# DevBoardSt107.net
KiCad netlist of a schematic drawn in Altium Designer
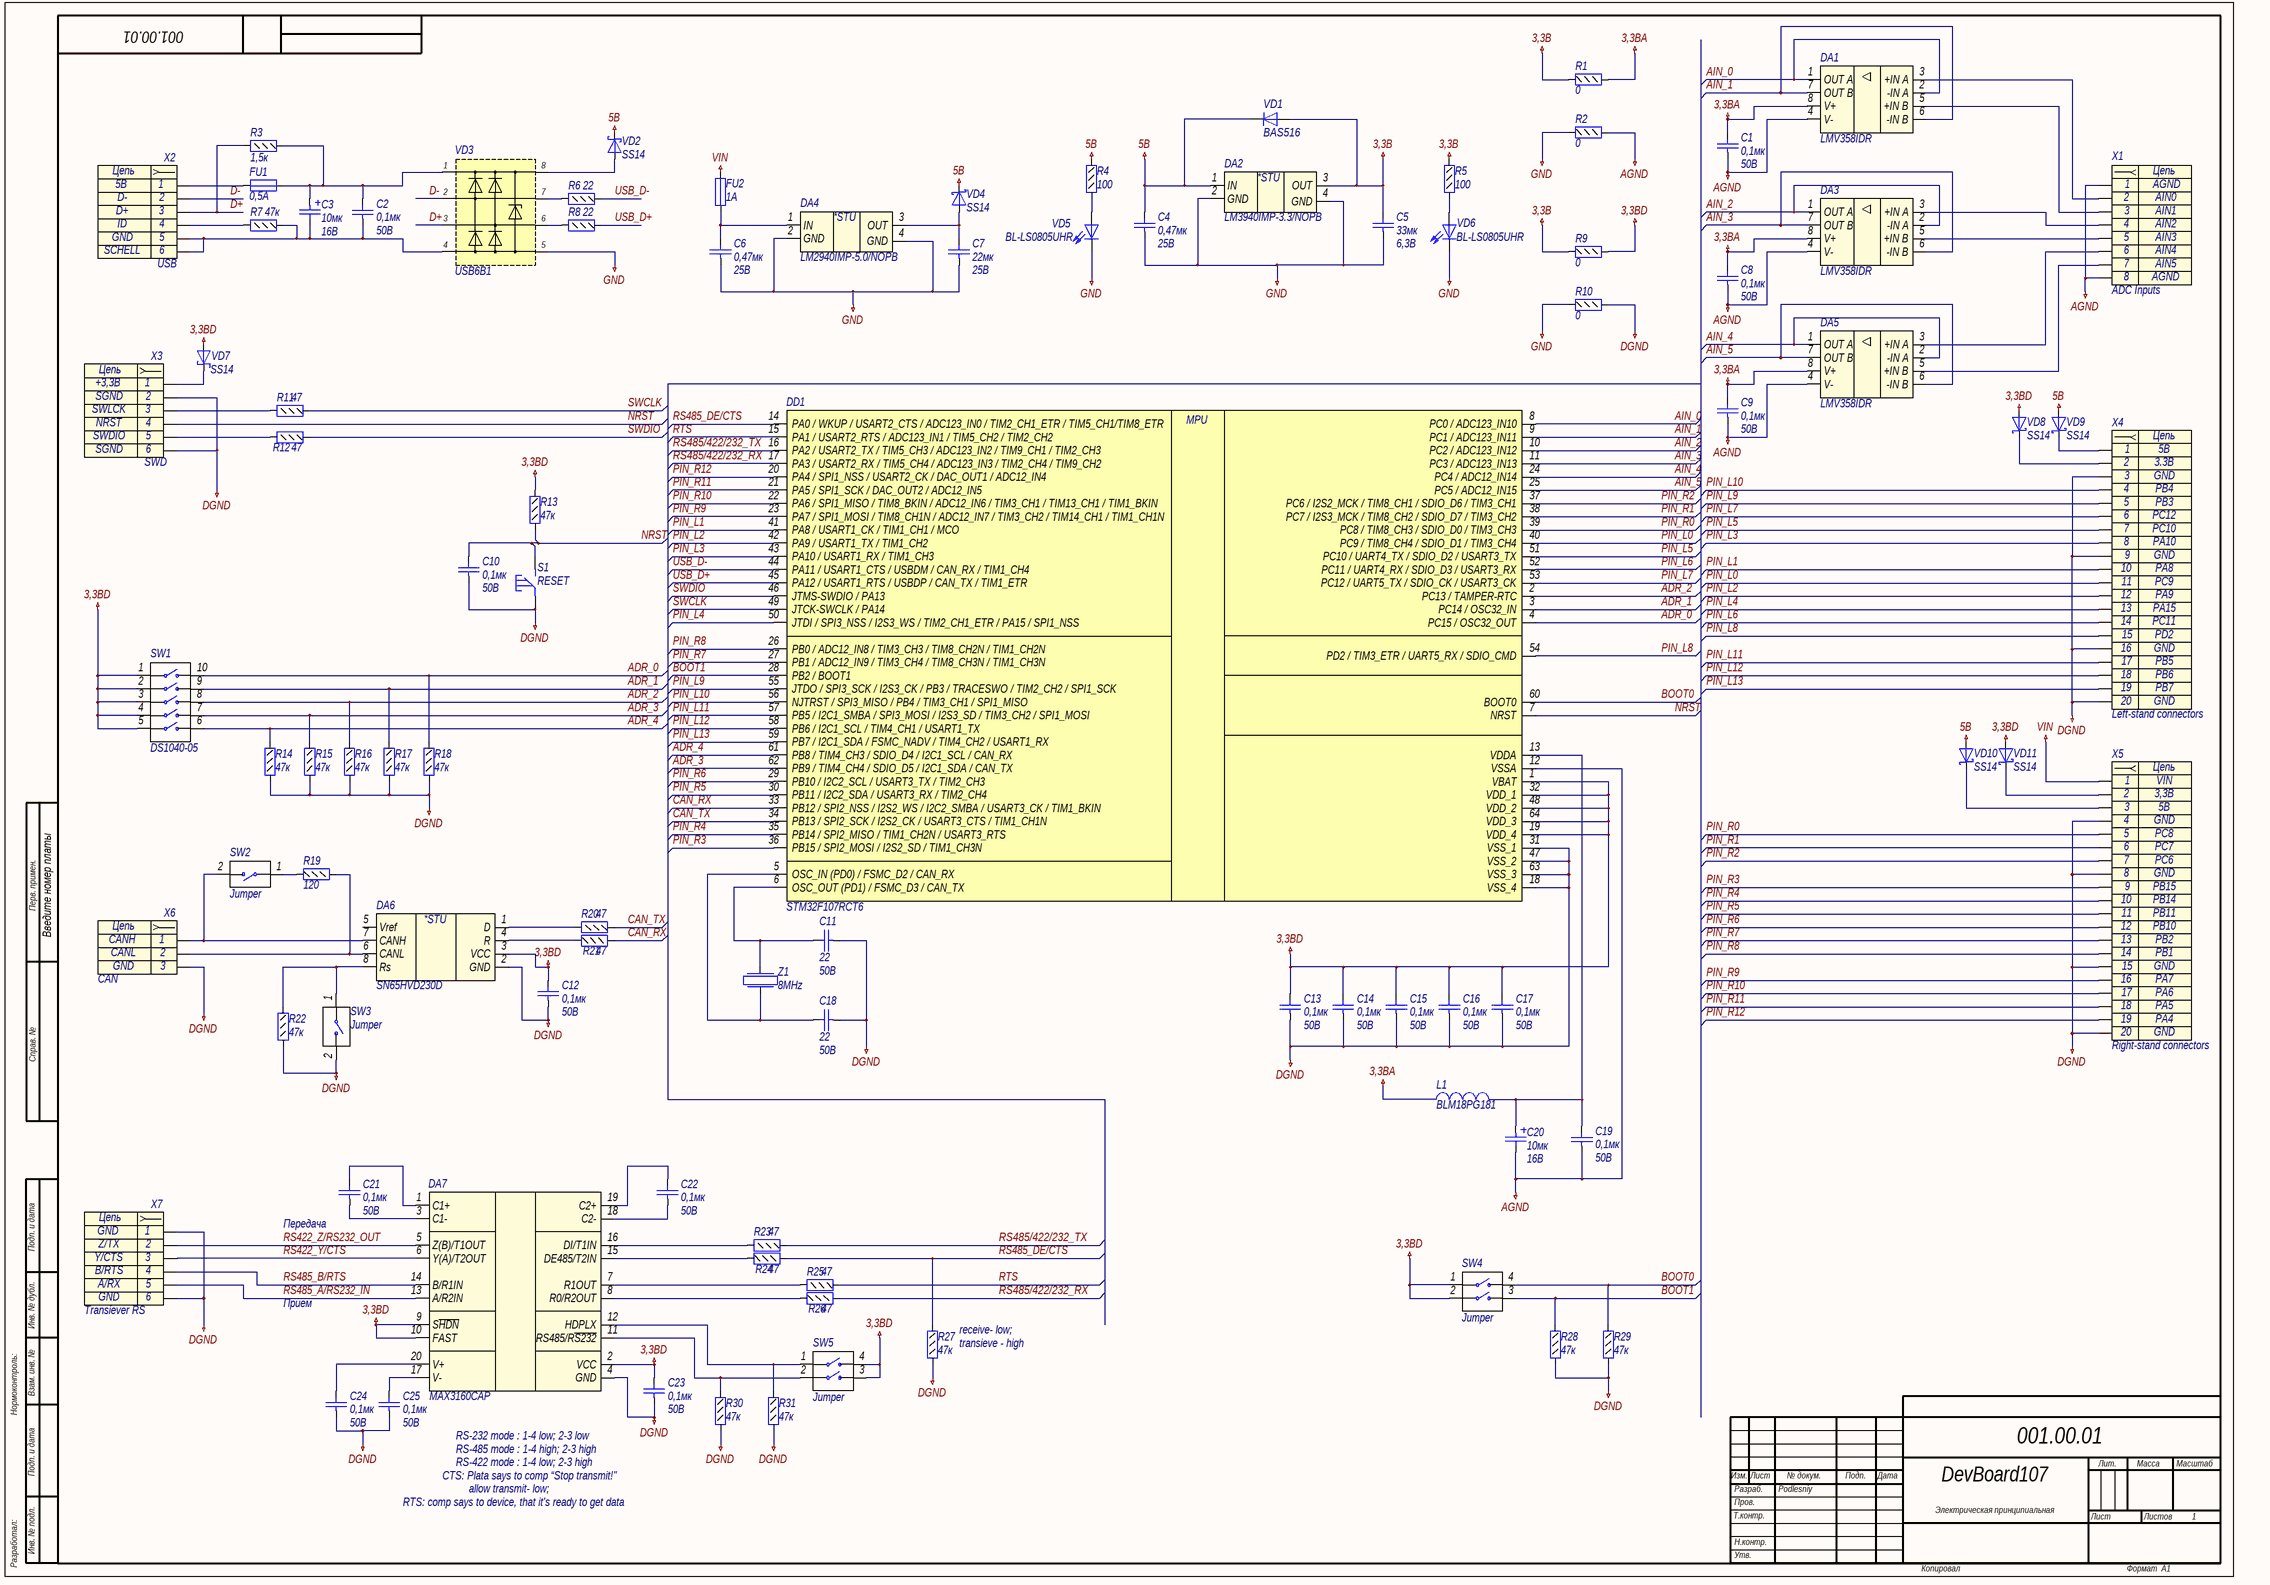
[diagram p0: DevBoardSt107.SchDoc]

(export (version "E")
  (design (tool "Eeschema 10.0.6"))
  (components
    (comp (ref "C1")
      (value "0,1мк")
      (footprint "ZabugorLib:C0603")
      (description "Конденсатор")
      (fields (field (name "VOLTAGE") "50В"))
      (libsource (lib "ZabugorLib") (part "Capacitor"))
    )
    (comp (ref "C2")
      (value "0,1мк")
      (footprint "ZabugorLib:C0603")
      (description "Конденсатор")
      (fields (field (name "VOLTAGE") "50В"))
      (libsource (lib "ZabugorLib") (part "Capacitor"))
    )
    (comp (ref "C3")
      (value "10мк")
      (footprint "ZabugorLib:TANTAL CASE B")
      (description "Конденсатор полярный")
      (fields (field (name "VOLTAGE") "16В"))
      (libsource (lib "ZabugorLib") (part "Capacitor_pol"))
    )
    (comp (ref "C4")
      (value "0,47мк")
      (footprint "ZabugorLib:C0603")
      (description "Конденсатор")
      (fields (field (name "VOLTAGE") "25В"))
      (libsource (lib "ZabugorLib") (part "Capacitor"))
    )
    (comp (ref "C5")
      (value "33мк")
      (footprint "ZabugorLib:C1210")
      (description "Конденсатор")
      (fields (field (name "VOLTAGE") "6,3В"))
      (libsource (lib "ZabugorLib") (part "Capacitor"))
    )
    (comp (ref "C6")
      (value "0,47мк")
      (footprint "ZabugorLib:C0603")
      (description "Конденсатор")
      (fields (field (name "VOLTAGE") "25В"))
      (libsource (lib "ZabugorLib") (part "Capacitor"))
    )
    (comp (ref "C7")
      (value "22мк")
      (footprint "ZabugorLib:C1210")
      (description "Конденсатор")
      (fields (field (name "VOLTAGE") "25В"))
      (libsource (lib "ZabugorLib") (part "Capacitor"))
    )
    (comp (ref "C8")
      (value "0,1мк")
      (footprint "ZabugorLib:C0603")
      (description "Конденсатор")
      (fields (field (name "VOLTAGE") "50В"))
      (libsource (lib "ZabugorLib") (part "Capacitor"))
    )
    (comp (ref "C9")
      (value "0,1мк")
      (footprint "ZabugorLib:C0603")
      (description "Конденсатор")
      (fields (field (name "VOLTAGE") "50В"))
      (libsource (lib "ZabugorLib") (part "Capacitor"))
    )
    (comp (ref "C10")
      (value "0,1мк")
      (footprint "ZabugorLib:C0603")
      (description "Конденсатор")
      (fields (field (name "VOLTAGE") "50В"))
      (libsource (lib "ZabugorLib") (part "Capacitor"))
    )
    (comp (ref "C11")
      (value "22")
      (footprint "ZabugorLib:C0603")
      (description "Конденсатор")
      (fields (field (name "VOLTAGE") "50В"))
      (libsource (lib "ZabugorLib") (part "Capacitor"))
    )
    (comp (ref "C12")
      (value "0,1мк")
      (footprint "ZabugorLib:C0603")
      (description "Конденсатор")
      (fields (field (name "VOLTAGE") "50В"))
      (libsource (lib "ZabugorLib") (part "Capacitor"))
    )
    (comp (ref "C13")
      (value "0,1мк")
      (footprint "ZabugorLib:C0603")
      (description "Конденсатор")
      (fields (field (name "VOLTAGE") "50В"))
      (libsource (lib "ZabugorLib") (part "Capacitor"))
    )
    (comp (ref "C14")
      (value "0,1мк")
      (footprint "ZabugorLib:C0603")
      (description "Конденсатор")
      (fields (field (name "VOLTAGE") "50В"))
      (libsource (lib "ZabugorLib") (part "Capacitor"))
    )
    (comp (ref "C15")
      (value "0,1мк")
      (footprint "ZabugorLib:C0603")
      (description "Конденсатор")
      (fields (field (name "VOLTAGE") "50В"))
      (libsource (lib "ZabugorLib") (part "Capacitor"))
    )
    (comp (ref "C16")
      (value "0,1мк")
      (footprint "ZabugorLib:C0603")
      (description "Конденсатор")
      (fields (field (name "VOLTAGE") "50В"))
      (libsource (lib "ZabugorLib") (part "Capacitor"))
    )
    (comp (ref "C17")
      (value "0,1мк")
      (footprint "ZabugorLib:C0603")
      (description "Конденсатор")
      (fields (field (name "VOLTAGE") "50В"))
      (libsource (lib "ZabugorLib") (part "Capacitor"))
    )
    (comp (ref "C18")
      (value "22")
      (footprint "ZabugorLib:C0603")
      (description "Конденсатор")
      (fields (field (name "VOLTAGE") "50В"))
      (libsource (lib "ZabugorLib") (part "Capacitor"))
    )
    (comp (ref "C19")
      (value "0,1мк")
      (footprint "ZabugorLib:C0603")
      (description "Конденсатор")
      (fields (field (name "VOLTAGE") "50В"))
      (libsource (lib "ZabugorLib") (part "Capacitor"))
    )
    (comp (ref "C20")
      (value "10мк")
      (footprint "ZabugorLib:TANTAL CASE B")
      (description "Конденсатор полярный")
      (fields (field (name "VOLTAGE") "16В"))
      (libsource (lib "ZabugorLib") (part "Capacitor_pol"))
    )
    (comp (ref "C21")
      (value "0,1мк")
      (footprint "ZabugorLib:C0603")
      (description "Конденсатор")
      (fields (field (name "VOLTAGE") "50В"))
      (libsource (lib "ZabugorLib") (part "Capacitor"))
    )
    (comp (ref "C22")
      (value "0,1мк")
      (footprint "ZabugorLib:C0603")
      (description "Конденсатор")
      (fields (field (name "VOLTAGE") "50В"))
      (libsource (lib "ZabugorLib") (part "Capacitor"))
    )
    (comp (ref "C23")
      (value "0,1мк")
      (footprint "ZabugorLib:C0603")
      (description "Конденсатор")
      (fields (field (name "VOLTAGE") "50В"))
      (libsource (lib "ZabugorLib") (part "Capacitor"))
    )
    (comp (ref "C24")
      (value "0,1мк")
      (footprint "ZabugorLib:C0603")
      (description "Конденсатор")
      (fields (field (name "VOLTAGE") "50В"))
      (libsource (lib "ZabugorLib") (part "Capacitor"))
    )
    (comp (ref "C25")
      (value "0,1мк")
      (footprint "ZabugorLib:C0603")
      (description "Конденсатор")
      (fields (field (name "VOLTAGE") "50В"))
      (libsource (lib "ZabugorLib") (part "Capacitor"))
    )
    (comp (ref "DA1")
      (value "LMV358IDR")
      (footprint "ZabugorLib:SO8")
      (description "Операционный усилитель ±6В")
      (libsource (lib "ZabugorLib") (part "LMV358IDR"))
    )
    (comp (ref "DA2")
      (value "LM3940IMP-3.3/NOPB")
      (footprint "ZabugorLib:SOT-223")
      (description "Low-Dropout Regulator for 5-V to 3.3-V Conversion")
      (libsource (lib "ZabugorLib") (part "LM3940"))
    )
    (comp (ref "DA3")
      (value "LMV358IDR")
      (footprint "ZabugorLib:SO8")
      (description "Операционный усилитель ±6В")
      (libsource (lib "ZabugorLib") (part "LMV358IDR"))
    )
    (comp (ref "DA4")
      (value "LM2940IMP-5.0/NOPB")
      (footprint "ZabugorLib:SOT-223")
      (description "Low-Dropout Regulator for 5-V to 3.3-V Conversion")
      (libsource (lib "ZabugorLib") (part "LM2940"))
    )
    (comp (ref "DA5")
      (value "LMV358IDR")
      (footprint "ZabugorLib:SO8")
      (description "Операционный усилитель ±6В")
      (libsource (lib "ZabugorLib") (part "LMV358IDR"))
    )
    (comp (ref "DA6")
      (value "SN65HVD230D")
      (footprint "ZabugorLib:SO8")
      (description "3,3V CAN TRANSCEIVERS")
      (libsource (lib "ZabugorLib") (part "SN65HVD23x"))
    )
    (comp (ref "DA7")
      (value "MAX3160CAP")
      (footprint "ZabugorLib:SSOP20")
      (description "райвер приемопередатчика RS232/RS422/RS485")
      (libsource (lib "ZabugorLib") (part "MAX3160"))
    )
    (comp (ref "DD1")
      (value "STM32F107RCT6")
      (footprint "ZabugorLib:LQFP64")
      (description "Микроконтроллер 64-pin")
      (fields (field (name "NAME") "STM32F107RCT6"))
      (libsource (lib "ZabugorLib") (part "STM32F107RCT6"))
    )
    (comp (ref "FU1")
      (value "0,5A")
      (footprint "FUSE812")
      (description "Предохранитель")
      (fields (field (name "Comment") "MF-MSMF050"))
      (libsource (lib "") (part "Fuse_1"))
    )
    (comp (ref "FU2")
      (value "1A")
      (footprint "FUSE812")
      (description "Предохранитель")
      (fields (field (name "Comment") "MF-MSMF075"))
      (libsource (lib "ZabugorLib") (part "Fuse"))
    )
    (comp (ref "L1")
      (value "XXX")
      (footprint "ZabugorLib:L0603")
      (description "Катушка индуктивности")
      (fields (field (name "NAME") "BLM18PG181"))
      (libsource (lib "ZabugorLib") (part "Inductor"))
    )
    (comp (ref "R1")
      (value "0")
      (footprint "ZabugorLib:R0603")
      (description "Резистор")
      (libsource (lib "") (part "Resistor_0,05Вт_1"))
    )
    (comp (ref "R2")
      (value "0")
      (footprint "ZabugorLib:R0603")
      (description "Резистор")
      (libsource (lib "") (part "Resistor_0,05Вт_1"))
    )
    (comp (ref "R3")
      (value "1,5к")
      (footprint "ZabugorLib:R0603")
      (description "Резистор")
      (libsource (lib "") (part "Resistor_0,05Вт_2"))
    )
    (comp (ref "R4")
      (value "100")
      (footprint "ZabugorLib:R0603")
      (description "Резистор")
      (libsource (lib "ZabugorLib") (part "Resistor_0,05Вт"))
    )
    (comp (ref "R5")
      (value "100")
      (footprint "ZabugorLib:R0603")
      (description "Резистор")
      (libsource (lib "ZabugorLib") (part "Resistor_0,05Вт"))
    )
    (comp (ref "R6")
      (value "22")
      (footprint "ZabugorLib:R0603")
      (description "Резистор")
      (libsource (lib "") (part "Resistor_0,05Вт_2"))
    )
    (comp (ref "R7")
      (value "47к")
      (footprint "ZabugorLib:R0603")
      (description "Резистор")
      (libsource (lib "") (part "Resistor_0,05Вт_2"))
    )
    (comp (ref "R8")
      (value "22")
      (footprint "ZabugorLib:R0603")
      (description "Резистор")
      (libsource (lib "") (part "Resistor_0,05Вт_2"))
    )
    (comp (ref "R9")
      (value "0")
      (footprint "ZabugorLib:R0603")
      (description "Резистор")
      (libsource (lib "") (part "Resistor_0,05Вт_1"))
    )
    (comp (ref "R10")
      (value "0")
      (footprint "ZabugorLib:R0603")
      (description "Резистор")
      (libsource (lib "") (part "Resistor_0,05Вт_1"))
    )
    (comp (ref "R11")
      (value "47")
      (footprint "ZabugorLib:R0603")
      (description "Резистор")
      (libsource (lib "") (part "Resistor_0,05Вт_2"))
    )
    (comp (ref "R12")
      (value "47")
      (footprint "ZabugorLib:R0603")
      (description "Резистор")
      (libsource (lib "") (part "Resistor_0,05Вт_2"))
    )
    (comp (ref "R13")
      (value "47к")
      (footprint "ZabugorLib:R0603")
      (description "Резистор")
      (libsource (lib "ZabugorLib") (part "Resistor_0,05Вт"))
    )
    (comp (ref "R14")
      (value "47к")
      (footprint "ZabugorLib:R0603")
      (description "Резистор")
      (libsource (lib "ZabugorLib") (part "Resistor_0,05Вт"))
    )
    (comp (ref "R15")
      (value "47к")
      (footprint "ZabugorLib:R0603")
      (description "Резистор")
      (libsource (lib "ZabugorLib") (part "Resistor_0,05Вт"))
    )
    (comp (ref "R16")
      (value "47к")
      (footprint "ZabugorLib:R0603")
      (description "Резистор")
      (libsource (lib "ZabugorLib") (part "Resistor_0,05Вт"))
    )
    (comp (ref "R17")
      (value "47к")
      (footprint "ZabugorLib:R0603")
      (description "Резистор")
      (libsource (lib "ZabugorLib") (part "Resistor_0,05Вт"))
    )
    (comp (ref "R18")
      (value "47к")
      (footprint "ZabugorLib:R0603")
      (description "Резистор")
      (libsource (lib "ZabugorLib") (part "Resistor_0,05Вт"))
    )
    (comp (ref "R19")
      (value "120")
      (footprint "ZabugorLib:R0603")
      (description "Резистор")
      (libsource (lib "") (part "Resistor_0,05Вт_1"))
    )
    (comp (ref "R20")
      (value "47")
      (footprint "ZabugorLib:R0603")
      (description "Резистор")
      (libsource (lib "") (part "Resistor_0,05Вт_2"))
    )
    (comp (ref "R21")
      (value "47")
      (footprint "ZabugorLib:R0603")
      (description "Резистор")
      (libsource (lib "") (part "Resistor_0,05Вт_1"))
    )
    (comp (ref "R22")
      (value "47к")
      (footprint "ZabugorLib:R0603")
      (description "Резистор")
      (libsource (lib "ZabugorLib") (part "Resistor_0,05Вт"))
    )
    (comp (ref "R23")
      (value "47")
      (footprint "ZabugorLib:R0603")
      (description "Резистор")
      (libsource (lib "") (part "Resistor_0,05Вт_2"))
    )
    (comp (ref "R24")
      (value "47")
      (footprint "ZabugorLib:R0603")
      (description "Резистор")
      (libsource (lib "") (part "Resistor_0,05Вт_1"))
    )
    (comp (ref "R25")
      (value "47")
      (footprint "ZabugorLib:R0603")
      (description "Резистор")
      (libsource (lib "") (part "Resistor_0,05Вт_2"))
    )
    (comp (ref "R26")
      (value "47")
      (footprint "ZabugorLib:R0603")
      (description "Резистор")
      (libsource (lib "") (part "Resistor_0,05Вт_1"))
    )
    (comp (ref "R27")
      (value "47к")
      (footprint "ZabugorLib:R0603")
      (description "Резистор")
      (libsource (lib "ZabugorLib") (part "Resistor_0,05Вт"))
    )
    (comp (ref "R28")
      (value "47к")
      (footprint "ZabugorLib:R0603")
      (description "Резистор")
      (libsource (lib "ZabugorLib") (part "Resistor_0,05Вт"))
    )
    (comp (ref "R29")
      (value "47к")
      (footprint "ZabugorLib:R0603")
      (description "Резистор")
      (libsource (lib "ZabugorLib") (part "Resistor_0,05Вт"))
    )
    (comp (ref "R30")
      (value "47к")
      (footprint "ZabugorLib:R0603")
      (description "Резистор")
      (libsource (lib "ZabugorLib") (part "Resistor_0,05Вт"))
    )
    (comp (ref "R31")
      (value "47к")
      (footprint "ZabugorLib:R0603")
      (description "Резистор")
      (libsource (lib "ZabugorLib") (part "Resistor_0,05Вт"))
    )
    (comp (ref "S1")
      (value "RESET")
      (footprint "ZabugorLib:DTSM 32")
      (description "Кнопка")
      (fields (field (name "NAME") "RESET"))
      (libsource (lib "ZabugorLib") (part "Button_SMD"))
    )
    (comp (ref "SW1")
      (value "DS1040-05")
      (footprint "ZabugorLib:DIP5")
      (description "DIP переключатель")
      (libsource (lib "ZabugorLib") (part "Switch 5-pin SMD"))
    )
    (comp (ref "SW2")
      (value "Jumper")
      (footprint "ZabugorLib:PLS2-2")
      (description "DIP переключатель")
      (libsource (lib "ZabugorLib") (part "Switch 1-pin SMD"))
    )
    (comp (ref "SW3")
      (value "Jumper")
      (footprint "ZabugorLib:PLS2-2")
      (description "DIP переключатель")
      (libsource (lib "ZabugorLib") (part "Switch 1-pin SMD"))
    )
    (comp (ref "SW4")
      (value "Jumper")
      (footprint "ZabugorLib:PLS2-4")
      (description "Переключатель адреса")
      (libsource (lib "ZabugorLib") (part "Switch 2-pin SMD"))
    )
    (comp (ref "SW5")
      (value "Jumper")
      (footprint "ZabugorLib:PLS2-4")
      (description "Переключатель адреса")
      (libsource (lib "ZabugorLib") (part "Switch 2-pin SMD"))
    )
    (comp (ref "VD1")
      (value "BAS516")
      (footprint "ZabugorLib:SOD523")
      (description "Диод")
      (libsource (lib "ZabugorLib") (part "Diode"))
    )
    (comp (ref "VD2")
      (value "SS14")
      (footprint "Zabugorlib:SMA")
      (description "Диод Шоттки")
      (libsource (lib "ZabugorLib") (part "DiodeSchottky"))
    )
    (comp (ref "VD3")
      (value "USB6B1")
      (footprint "ZabugorLib:SO8")
      (description "Защита линии данных")
      (fields (field (name "NAME") "USB6B1"))
      (libsource (lib "ZabugorLib") (part "USB6B1"))
    )
    (comp (ref "VD4")
      (value "SS14")
      (footprint "Zabugorlib:SMA")
      (description "Диод Шоттки")
      (libsource (lib "ZabugorLib") (part "DiodeSchottky"))
    )
    (comp (ref "VD5")
      (value "BL-LS0805UHR")
      (footprint "ZabugorLib:D0805")
      (description "Светодиод")
      (fields (field (name "NAME") "BL-LS0805UHR"))
      (libsource (lib "ZabugorLib") (part "LED_L"))
    )
    (comp (ref "VD6")
      (value "BL-LS0805UHR")
      (footprint "ZabugorLib:D0805")
      (description "Светодиод")
      (fields (field (name "NAME") "BL-LS0805UHR"))
      (libsource (lib "ZabugorLib") (part "LED_L"))
    )
    (comp (ref "VD7")
      (value "SS14")
      (footprint "Zabugorlib:SMA")
      (description "Диод Шоттки")
      (libsource (lib "ZabugorLib") (part "DiodeSchottky"))
    )
    (comp (ref "VD8")
      (value "SS14")
      (footprint "Zabugorlib:SMA")
      (description "Диод Шоттки")
      (libsource (lib "ZabugorLib") (part "DiodeSchottky"))
    )
    (comp (ref "VD9")
      (value "SS14")
      (footprint "Zabugorlib:SMA")
      (description "Диод Шоттки")
      (libsource (lib "ZabugorLib") (part "DiodeSchottky"))
    )
    (comp (ref "VD10")
      (value "SS14")
      (footprint "Zabugorlib:SMA")
      (description "Диод Шоттки")
      (libsource (lib "ZabugorLib") (part "DiodeSchottky"))
    )
    (comp (ref "VD11")
      (value "SS14")
      (footprint "Zabugorlib:SMA")
      (description "Диод Шоттки")
      (libsource (lib "ZabugorLib") (part "DiodeSchottky"))
    )
    (comp (ref "X1")
      (value "ADC Inputs")
      (footprint "ZabugorLib:PLS-8")
      (description "Разъем - 8 конт. розетка")
      (libsource (lib "ZabugorLib") (part "Header_8_sct"))
    )
    (comp (ref "X2")
      (value "USB")
      (footprint "ZabugorLib:USB-B Micro")
      (description "Разъем - 5 конт. розетка")
      (libsource (lib "ZabugorLib") (part "Header_6_sct"))
    )
    (comp (ref "X3")
      (value "SWD")
      (footprint "ZabugorLib:PLS2-6")
      (description "Разъем - 5 конт. розетка")
      (libsource (lib "ZabugorLib") (part "Header_6_sct"))
    )
    (comp (ref "X4")
      (value "Left-stand connectors")
      (footprint "ZabugorLib:PLS-20-2")
      (description "Разъем - 20 конт. розетка")
      (libsource (lib "ZabugorLib") (part "Header_20"))
    )
    (comp (ref "X5")
      (value "Right-stand connectors")
      (footprint "ZabugorLib:PLS-20-2")
      (description "Разъем - 20 конт. розетка")
      (libsource (lib "ZabugorLib") (part "Header_20"))
    )
    (comp (ref "X6")
      (value "CAN")
      (footprint "ZabugorLib:TERMINAL 3 way-2.54mm")
      (description "Разъем - 2 конт. розетка")
      (libsource (lib "ZabugorLib") (part "Header_3_sct"))
    )
    (comp (ref "X7")
      (value "Transiever RS")
      (footprint "ZabugorLib:TERMINAL 6 way-2.54mm")
      (description "Разъем - 5 конт. розетка")
      (libsource (lib "ZabugorLib") (part "Header_6_sct"))
    )
    (comp (ref "Z1")
      (value "8MHz")
      (footprint "ZabugorLib:QSMD5.0x3.2x1.0")
      (description "Кварцевый резонатор")
      (libsource (lib "ZabugorLib") (part "Crystal"))
    )
  )
  (nets
    (net (code "1") (name "/ADR_0") (class "Default")
      (node (ref "DD1") (pin "4") (pinfunction "PC15_/_OSC32_OUT_4") (pintype "passive"))
      (node (ref "R18") (pin "2") (pinfunction "5_2") (pintype "passive"))
      (node (ref "SW1") (pin "10") (pintype "passive"))
    )
    (net (code "2") (name "/ADR_1") (class "Default")
      (node (ref "DD1") (pin "3") (pinfunction "PC14_/_OSC32_IN_3") (pintype "passive"))
      (node (ref "R17") (pin "2") (pinfunction "5_2") (pintype "passive"))
      (node (ref "SW1") (pin "9") (pintype "passive"))
    )
    (net (code "3") (name "/ADR_2") (class "Default")
      (node (ref "DD1") (pin "2") (pinfunction "PC13_/_TAMPER-RTC_2") (pintype "passive"))
      (node (ref "R16") (pin "2") (pinfunction "5_2") (pintype "passive"))
      (node (ref "SW1") (pin "8") (pintype "passive"))
    )
    (net (code "4") (name "/ADR_3") (class "Default")
      (node (ref "DD1") (pin "62") (pinfunction "PB9_/_TIM4_CH4_/_SDIO_D5_/_I2C1_SDA_/_CAN_TX_62") (pintype "passive"))
      (node (ref "R15") (pin "2") (pinfunction "5_2") (pintype "passive"))
      (node (ref "SW1") (pin "7") (pintype "passive"))
    )
    (net (code "5") (name "/ADR_4") (class "Default")
      (node (ref "DD1") (pin "61") (pinfunction "PB8_/_TIM4_CH3_/_SDIO_D4_/_I2C1_SCL_/_CAN_RX_61") (pintype "passive"))
      (node (ref "R14") (pin "2") (pinfunction "5_2") (pintype "passive"))
      (node (ref "SW1") (pin "6") (pintype "passive"))
    )
    (net (code "6") (name "/AIN_0") (class "Default")
      (node (ref "DA1") (pin "1") (pinfunction "OUT_A_1") (pintype "passive"))
      (node (ref "DA1") (pin "2") (pinfunction "-IN_A_2") (pintype "passive"))
      (node (ref "DD1") (pin "8") (pinfunction "PC0_/_ADC123_IN10_8") (pintype "passive"))
    )
    (net (code "7") (name "/AIN_1") (class "Default")
      (node (ref "DA1") (pin "6") (pinfunction "-IN_B_6") (pintype "passive"))
      (node (ref "DA1") (pin "7") (pinfunction "OUT_B_7") (pintype "passive"))
      (node (ref "DD1") (pin "9") (pinfunction "PC1_/_ADC123_IN11_9") (pintype "passive"))
    )
    (net (code "8") (name "/AIN_2") (class "Default")
      (node (ref "DA3") (pin "1") (pinfunction "OUT_A_1") (pintype "passive"))
      (node (ref "DA3") (pin "2") (pinfunction "-IN_A_2") (pintype "passive"))
      (node (ref "DD1") (pin "10") (pinfunction "PC2_/_ADC123_IN12_10") (pintype "passive"))
    )
    (net (code "9") (name "/AIN_3") (class "Default")
      (node (ref "DA3") (pin "6") (pinfunction "-IN_B_6") (pintype "passive"))
      (node (ref "DA3") (pin "7") (pinfunction "OUT_B_7") (pintype "passive"))
      (node (ref "DD1") (pin "11") (pinfunction "PC3_/_ADC123_IN13_11") (pintype "passive"))
    )
    (net (code "10") (name "/AIN_4") (class "Default")
      (node (ref "DA5") (pin "1") (pinfunction "OUT_A_1") (pintype "passive"))
      (node (ref "DA5") (pin "2") (pinfunction "-IN_A_2") (pintype "passive"))
      (node (ref "DD1") (pin "24") (pinfunction "PC4_/_ADC12_IN14_24") (pintype "passive"))
    )
    (net (code "11") (name "/AIN_5") (class "Default")
      (node (ref "DA5") (pin "6") (pinfunction "-IN_B_6") (pintype "passive"))
      (node (ref "DA5") (pin "7") (pinfunction "OUT_B_7") (pintype "passive"))
      (node (ref "DD1") (pin "25") (pinfunction "PC5_/_ADC12_IN15_25") (pintype "passive"))
    )
    (net (code "12") (name "/BOOT0") (class "Default")
      (node (ref "DD1") (pin "60") (pinfunction "BOOT0_60") (pintype "passive"))
      (node (ref "R29") (pin "2") (pinfunction "5_2") (pintype "passive"))
      (node (ref "SW4") (pin "4") (pintype "passive"))
    )
    (net (code "13") (name "/BOOT1") (class "Default")
      (node (ref "DD1") (pin "28") (pinfunction "PB2_/_BOOT1_28") (pintype "passive"))
      (node (ref "R28") (pin "2") (pinfunction "5_2") (pintype "passive"))
      (node (ref "SW4") (pin "3") (pintype "passive"))
    )
    (net (code "14") (name "/CAN_RX") (class "Default")
      (node (ref "DD1") (pin "33") (pinfunction "PB12_/_SPI2_NSS_/_I2S2_WS_/_I2C2_SMBA_/_USART3_CK_/_TIM1_BKIN_33") (pintype "passive"))
      (node (ref "R21") (pin "1") (pinfunction "1_1") (pintype "passive"))
    )
    (net (code "15") (name "/CAN_TX") (class "Default")
      (node (ref "DD1") (pin "34") (pinfunction "PB13_/_SPI2_SCK_/_I2S2_CK_/_USART3_CTS_/_TIM1_CH1N_34") (pintype "passive"))
      (node (ref "R20") (pin "2") (pinfunction "5_2") (pintype "passive"))
    )
    (net (code "16") (name "/D+") (class "Default")
      (node (ref "R3") (pin "1") (pinfunction "1_1") (pintype "passive"))
      (node (ref "VD3") (pin "3") (pintype "passive"))
      (node (ref "X2") (pin "3") (pinfunction "3_3") (pintype "passive"))
    )
    (net (code "17") (name "/D-") (class "Default")
      (node (ref "VD3") (pin "2") (pintype "passive"))
      (node (ref "X2") (pin "2") (pinfunction "2_2") (pintype "passive"))
    )
    (net (code "18") (name "/NRST") (class "Default")
      (node (ref "C10") (pin "2") (pinfunction "2_2") (pintype "passive"))
      (node (ref "DD1") (pin "7") (pinfunction "NRST_7") (pintype "passive"))
      (node (ref "R13") (pin "1") (pinfunction "1_1") (pintype "passive"))
      (node (ref "S1") (pin "4") (pinfunction "4_4") (pintype "passive"))
      (node (ref "X3") (pin "4") (pinfunction "4_4") (pintype "passive"))
    )
    (net (code "19") (name "/PIN_L0") (class "Default")
      (node (ref "DD1") (pin "40") (pinfunction "PC9_/_TIM8_CH4_/_SDIO_D1_/_TIM3_CH4_40") (pintype "passive"))
      (node (ref "X4") (pin "11") (pinfunction "11_11") (pintype "passive"))
    )
    (net (code "20") (name "/PIN_L1") (class "Default")
      (node (ref "DD1") (pin "41") (pinfunction "PA8_/_USART1_CK_/_TIM1_CH1_/_MCO_41") (pintype "passive"))
      (node (ref "X4") (pin "10") (pinfunction "10_10") (pintype "passive"))
    )
    (net (code "21") (name "/PIN_L2") (class "Default")
      (node (ref "DD1") (pin "42") (pinfunction "PA9_/_USART1_TX_/_TIM1_CH2_42") (pintype "passive"))
      (node (ref "X4") (pin "12") (pinfunction "12_12") (pintype "passive"))
    )
    (net (code "22") (name "/PIN_L3") (class "Default")
      (node (ref "DD1") (pin "43") (pinfunction "PA10_/_USART1_RX_/_TIM1_CH3_43") (pintype "passive"))
      (node (ref "X4") (pin "8") (pinfunction "8_8") (pintype "passive"))
    )
    (net (code "23") (name "/PIN_L4") (class "Default")
      (node (ref "DD1") (pin "50") (pinfunction "JTDI_/_SPI3_NSS_/_I2S3_WS_/_TIM2_CH1_ETR_/_PA15_/_SPI1_NSS_50") (pintype "passive"))
      (node (ref "X4") (pin "13") (pinfunction "13_13") (pintype "passive"))
    )
    (net (code "24") (name "/PIN_L5") (class "Default")
      (node (ref "DD1") (pin "51") (pinfunction "PC10_/_UART4_TX_/_SDIO_D2_/_USART3_TX_51") (pintype "passive"))
      (node (ref "X4") (pin "7") (pinfunction "7_7") (pintype "passive"))
    )
    (net (code "25") (name "/PIN_L6") (class "Default")
      (node (ref "DD1") (pin "52") (pinfunction "PC11_/_UART4_RX_/_SDIO_D3_/_USART3_RX_52") (pintype "passive"))
      (node (ref "X4") (pin "14") (pinfunction "14_14") (pintype "passive"))
    )
    (net (code "26") (name "/PIN_L7") (class "Default")
      (node (ref "DD1") (pin "53") (pinfunction "PC12_/_UART5_TX_/_SDIO_CK_/_USART3_CK_53") (pintype "passive"))
      (node (ref "X4") (pin "6") (pinfunction "6_6") (pintype "passive"))
    )
    (net (code "27") (name "/PIN_L8") (class "Default")
      (node (ref "DD1") (pin "54") (pinfunction "PD2_/_TIM3_ETR_/_UART5_RX_/_SDIO_CMD_54") (pintype "passive"))
      (node (ref "X4") (pin "15") (pinfunction "15_15") (pintype "passive"))
    )
    (net (code "28") (name "/PIN_L9") (class "Default")
      (node (ref "DD1") (pin "55") (pinfunction "JTDO_/_SPI3_SCK_/_I2S3_CK_/_PB3_/_TRACESWO_/_TIM2_CH2_/_SPI1_SCK_55") (pintype "passive"))
      (node (ref "X4") (pin "5") (pinfunction "5_5") (pintype "passive"))
    )
    (net (code "29") (name "/PIN_L10") (class "Default")
      (node (ref "DD1") (pin "56") (pinfunction "NJTRST_/_SPI3_MISO_/_PB4_/_TIM3_CH1_/_SPI1_MISO_56") (pintype "passive"))
      (node (ref "X4") (pin "4") (pinfunction "4_4") (pintype "passive"))
    )
    (net (code "30") (name "/PIN_L11") (class "Default")
      (node (ref "DD1") (pin "57") (pinfunction "PB5_/_I2C1_SMBA_/_SPI3_MOSI_/_I2S3_SD_/_TIM3_CH2_/_SPI1_MOSI_57") (pintype "passive"))
      (node (ref "X4") (pin "17") (pinfunction "17_17") (pintype "passive"))
    )
    (net (code "31") (name "/PIN_L12") (class "Default")
      (node (ref "DD1") (pin "58") (pinfunction "PB6_/_I2C1_SCL_/_TIM4_CH1_/_USART1_TX_58") (pintype "passive"))
      (node (ref "X4") (pin "18") (pinfunction "18_18") (pintype "passive"))
    )
    (net (code "32") (name "/PIN_L13") (class "Default")
      (node (ref "DD1") (pin "59") (pinfunction "PB7_/_I2C1_SDA_/_FSMC_NADV_/_TIM4_CH2_/_USART1_RX_59") (pintype "passive"))
      (node (ref "X4") (pin "19") (pinfunction "19_19") (pintype "passive"))
    )
    (net (code "33") (name "/PIN_R0") (class "Default")
      (node (ref "DD1") (pin "39") (pinfunction "PC8_/_TIM8_CH3_/_SDIO_D0_/_TIM3_CH3_39") (pintype "passive"))
      (node (ref "X5") (pin "5") (pinfunction "5_5") (pintype "passive"))
    )
    (net (code "34") (name "/PIN_R1") (class "Default")
      (node (ref "DD1") (pin "38") (pinfunction "PC7_/_I2S3_MCK_/_TIM8_CH2_/_SDIO_D7_/_TIM3_CH2_38") (pintype "passive"))
      (node (ref "X5") (pin "6") (pinfunction "6_6") (pintype "passive"))
    )
    (net (code "35") (name "/PIN_R2") (class "Default")
      (node (ref "DD1") (pin "37") (pinfunction "PC6_/_I2S2_MCK_/_TIM8_CH1_/_SDIO_D6_/_TIM3_CH1_37") (pintype "passive"))
      (node (ref "X5") (pin "7") (pinfunction "7_7") (pintype "passive"))
    )
    (net (code "36") (name "/PIN_R3") (class "Default")
      (node (ref "DD1") (pin "36") (pinfunction "PB15_/_SPI2_MOSI_/_I2S2_SD_/_TIM1_CH3N_36") (pintype "passive"))
      (node (ref "X5") (pin "9") (pinfunction "9_9") (pintype "passive"))
    )
    (net (code "37") (name "/PIN_R4") (class "Default")
      (node (ref "DD1") (pin "35") (pinfunction "PB14_/_SPI2_MISO_/_TIM1_CH2N_/_USART3_RTS_35") (pintype "passive"))
      (node (ref "X5") (pin "10") (pinfunction "10_10") (pintype "passive"))
    )
    (net (code "38") (name "/PIN_R5") (class "Default")
      (node (ref "DD1") (pin "30") (pinfunction "PB11_/_I2C2_SDA_/_USART3_RX_/_TIM2_CH4_30") (pintype "passive"))
      (node (ref "X5") (pin "11") (pinfunction "11_11") (pintype "passive"))
    )
    (net (code "39") (name "/PIN_R6") (class "Default")
      (node (ref "DD1") (pin "29") (pinfunction "PB10_/_I2C2_SCL_/_USART3_TX_/_TIM2_CH3_29") (pintype "passive"))
      (node (ref "X5") (pin "12") (pinfunction "12_12") (pintype "passive"))
    )
    (net (code "40") (name "/PIN_R7") (class "Default")
      (node (ref "DD1") (pin "27") (pinfunction "PB1_/_ADC12_IN9_/_TIM3_CH4_/_TIM8_CH3N_/_TIM1_CH3N_27") (pintype "passive"))
      (node (ref "X5") (pin "13") (pinfunction "13_13") (pintype "passive"))
    )
    (net (code "41") (name "/PIN_R8") (class "Default")
      (node (ref "DD1") (pin "26") (pinfunction "PB0_/_ADC12_IN8_/_TIM3_CH3_/_TIM8_CH2N_/_TIM1_CH2N_26") (pintype "passive"))
      (node (ref "X5") (pin "14") (pinfunction "14_14") (pintype "passive"))
    )
    (net (code "42") (name "/PIN_R9") (class "Default")
      (node (ref "DD1") (pin "23") (pinfunction "PA7_/_SPI1_MOSI_/_TIM8_CH1N_/_ADC12_IN7_/_TIM3_CH2_/_TIM14_CH1_/_TIM1_CH1N_23") (pintype "passive"))
      (node (ref "X5") (pin "16") (pinfunction "16_16") (pintype "passive"))
    )
    (net (code "43") (name "/PIN_R10") (class "Default")
      (node (ref "DD1") (pin "22") (pinfunction "PA6_/_SPI1_MISO_/_TIM8_BKIN_/_ADC12_IN6_/_TIM3_CH1_/_TIM13_CH1_/_TIM1_BKIN_22") (pintype "passive"))
      (node (ref "X5") (pin "17") (pinfunction "17_17") (pintype "passive"))
    )
    (net (code "44") (name "/PIN_R11") (class "Default")
      (node (ref "DD1") (pin "21") (pinfunction "PA5_/_SPI1_SCK_/_DAC_OUT2_/_ADC12_IN5_21") (pintype "passive"))
      (node (ref "X5") (pin "18") (pinfunction "18_18") (pintype "passive"))
    )
    (net (code "45") (name "/PIN_R12") (class "Default")
      (node (ref "DD1") (pin "20") (pinfunction "PA4_/_SPI1_NSS_/_USART2_CK_/_DAC_OUT1_/_ADC12_IN4_20") (pintype "passive"))
      (node (ref "X5") (pin "19") (pinfunction "19_19") (pintype "passive"))
    )
    (net (code "46") (name "/RS422_Y{slash}CTS") (class "Default")
      (node (ref "DA7") (pin "6") (pinfunction "Y(A)/T2OUT_6") (pintype "power_in"))
      (node (ref "X7") (pin "3") (pinfunction "3_3") (pintype "passive"))
    )
    (net (code "47") (name "/RS422_Z{slash}RS232_OUT") (class "Default")
      (node (ref "DA7") (pin "5") (pinfunction "Z(B)/T1OUT_5") (pintype "power_in"))
      (node (ref "X7") (pin "2") (pinfunction "2_2") (pintype "passive"))
    )
    (net (code "48") (name "/RS485_A{slash}RS232_IN") (class "Default")
      (node (ref "DA7") (pin "13") (pinfunction "A/R2IN_13") (pintype "power_in"))
      (node (ref "X7") (pin "5") (pinfunction "5_5") (pintype "passive"))
    )
    (net (code "49") (name "/RS485_B{slash}RTS") (class "Default")
      (node (ref "DA7") (pin "14") (pinfunction "B/R1IN_14") (pintype "power_in"))
      (node (ref "X7") (pin "4") (pinfunction "4_4") (pintype "passive"))
    )
    (net (code "50") (name "/RS485_DE{slash}CTS") (class "Default")
      (node (ref "DD1") (pin "14") (pinfunction "PA0_/_WKUP_/_USART2_CTS_/_ADC123_IN0_/_TIM2_CH1_ETR_/_TIM5_CH1/TIM8_ETR_14") (pintype "passive"))
      (node (ref "R24") (pin "1") (pinfunction "1_1") (pintype "passive"))
      (node (ref "R27") (pin "2") (pinfunction "5_2") (pintype "passive"))
    )
    (net (code "51") (name "/RS485{slash}422{slash}232_RX") (class "Default")
      (node (ref "DD1") (pin "17") (pinfunction "PA3_/_USART2_RX_/_TIM5_CH4_/_ADC123_IN3_/_TIM2_CH4_/_TIM9_CH2_17") (pintype "passive"))
      (node (ref "R26") (pin "1") (pinfunction "1_1") (pintype "passive"))
    )
    (net (code "52") (name "/RS485{slash}422{slash}232_TX") (class "Default")
      (node (ref "DD1") (pin "16") (pinfunction "PA2_/_USART2_TX_/_TIM5_CH3_/_ADC123_IN2_/_TIM9_CH1_/_TIM2_CH3_16") (pintype "passive"))
      (node (ref "R23") (pin "2") (pinfunction "5_2") (pintype "passive"))
    )
    (net (code "53") (name "/RTS") (class "Default")
      (node (ref "DD1") (pin "15") (pinfunction "PA1_/_USART2_RTS_/_ADC123_IN1_/_TIM5_CH2_/_TIM2_CH2_15") (pintype "passive"))
      (node (ref "R25") (pin "2") (pinfunction "5_2") (pintype "passive"))
    )
    (net (code "54") (name "/SWCLK") (class "Default")
      (node (ref "DD1") (pin "49") (pinfunction "JTCK-SWCLK_/_PA14_49") (pintype "passive"))
      (node (ref "R11") (pin "2") (pinfunction "5_2") (pintype "passive"))
    )
    (net (code "55") (name "/SWDIO") (class "Default")
      (node (ref "DD1") (pin "46") (pinfunction "JTMS-SWDIO_/_PA13_46") (pintype "passive"))
      (node (ref "R12") (pin "2") (pinfunction "5_2") (pintype "passive"))
    )
    (net (code "56") (name "/USB_D+") (class "Default")
      (node (ref "DD1") (pin "45") (pinfunction "PA12_/_USART1_RTS_/_USBDP_/_CAN_TX_/_TIM1_ETR_45") (pintype "passive"))
      (node (ref "R8") (pin "2") (pinfunction "5_2") (pintype "passive"))
    )
    (net (code "57") (name "/USB_D-") (class "Default")
      (node (ref "DD1") (pin "44") (pinfunction "PA11_/_USART1_CTS_/_USBDM_/_CAN_RX_/_TIM1_CH4_44") (pintype "passive"))
      (node (ref "R6") (pin "2") (pinfunction "5_2") (pintype "passive"))
    )
    (net (code "58") (name "3,3В") (class "Default")
      (node (ref "C5") (pin "2") (pinfunction "2_2") (pintype "passive"))
      (node (ref "DA2") (pin "3") (pinfunction "OUT_3") (pintype "power_in"))
      (node (ref "R1") (pin "2") (pinfunction "5_2") (pintype "passive"))
      (node (ref "R5") (pin "2") (pinfunction "5_2") (pintype "passive"))
      (node (ref "R9") (pin "2") (pinfunction "5_2") (pintype "passive"))
      (node (ref "VD1") (pin "2") (pinfunction "A_2") (pintype "passive"))
    )
    (net (code "59") (name "3,3ВA") (class "Default")
      (node (ref "C1") (pin "2") (pinfunction "2_2") (pintype "passive"))
      (node (ref "C8") (pin "2") (pinfunction "2_2") (pintype "passive"))
      (node (ref "C9") (pin "2") (pinfunction "2_2") (pintype "passive"))
      (node (ref "DA1") (pin "8") (pinfunction "V+_8") (pintype "passive"))
      (node (ref "DA3") (pin "8") (pinfunction "V+_8") (pintype "passive"))
      (node (ref "DA5") (pin "8") (pinfunction "V+_8") (pintype "passive"))
      (node (ref "L1") (pin "1") (pinfunction "1_1") (pintype "passive"))
      (node (ref "R1") (pin "1") (pinfunction "1_1") (pintype "passive"))
    )
    (net (code "60") (name "3,3ВD") (class "Default")
      (node (ref "C12") (pin "2") (pinfunction "2_2") (pintype "passive"))
      (node (ref "C13") (pin "2") (pinfunction "2_2") (pintype "passive"))
      (node (ref "C14") (pin "2") (pinfunction "2_2") (pintype "passive"))
      (node (ref "C15") (pin "2") (pinfunction "2_2") (pintype "passive"))
      (node (ref "C16") (pin "2") (pinfunction "2_2") (pintype "passive"))
      (node (ref "C17") (pin "2") (pinfunction "2_2") (pintype "passive"))
      (node (ref "C23") (pin "2") (pinfunction "2_2") (pintype "passive"))
      (node (ref "DA6") (pin "3") (pinfunction "VCC_3") (pintype "power_in"))
      (node (ref "DA7") (pin "10") (pinfunction "FAST_10") (pintype "power_in"))
      (node (ref "DA7") (pin "2") (pinfunction "VCC_2") (pintype "power_in"))
      (node (ref "DA7") (pin "9") (pinfunction "S~{HDN}_9") (pintype "power_in"))
      (node (ref "DD1") (pin "1") (pinfunction "VBAT_1") (pintype "passive"))
      (node (ref "DD1") (pin "19") (pinfunction "VDD_4_19") (pintype "passive"))
      (node (ref "DD1") (pin "32") (pinfunction "VDD_1_32") (pintype "passive"))
      (node (ref "DD1") (pin "48") (pinfunction "VDD_2_48") (pintype "passive"))
      (node (ref "DD1") (pin "64") (pinfunction "VDD_3_64") (pintype "passive"))
      (node (ref "R13") (pin "2") (pinfunction "5_2") (pintype "passive"))
      (node (ref "R9") (pin "1") (pinfunction "1_1") (pintype "passive"))
      (node (ref "SW1") (pin "1") (pintype "passive"))
      (node (ref "SW1") (pin "2") (pintype "passive"))
      (node (ref "SW1") (pin "3") (pintype "passive"))
      (node (ref "SW1") (pin "4") (pintype "passive"))
      (node (ref "SW1") (pin "5") (pintype "passive"))
      (node (ref "SW4") (pin "1") (pintype "passive"))
      (node (ref "SW4") (pin "2") (pintype "passive"))
      (node (ref "SW5") (pin "3") (pintype "passive"))
      (node (ref "SW5") (pin "4") (pintype "passive"))
      (node (ref "VD11") (pin "2") (pinfunction "A_2") (pintype "passive"))
      (node (ref "VD7") (pin "2") (pinfunction "A_2") (pintype "passive"))
      (node (ref "VD8") (pin "2") (pinfunction "A_2") (pintype "passive"))
    )
    (net (code "61") (name "5В") (class "Default")
      (node (ref "C4") (pin "2") (pinfunction "2_2") (pintype "passive"))
      (node (ref "DA2") (pin "1") (pinfunction "IN_1") (pintype "power_in"))
      (node (ref "R4") (pin "2") (pinfunction "5_2") (pintype "passive"))
      (node (ref "VD1") (pin "1") (pinfunction "K_1") (pintype "passive"))
      (node (ref "VD10") (pin "2") (pinfunction "A_2") (pintype "passive"))
      (node (ref "VD2") (pin "1") (pinfunction "K_1") (pintype "passive"))
      (node (ref "VD4") (pin "1") (pinfunction "K_1") (pintype "passive"))
      (node (ref "VD9") (pin "2") (pinfunction "A_2") (pintype "passive"))
    )
    (net (code "62") (name "AGND") (class "Default")
      (node (ref "C1") (pin "1") (pinfunction "1_1") (pintype "passive"))
      (node (ref "C19") (pin "1") (pinfunction "1_1") (pintype "passive"))
      (node (ref "C20") (pin "2") (pinfunction "2_2") (pintype "passive"))
      (node (ref "C8") (pin "1") (pinfunction "1_1") (pintype "passive"))
      (node (ref "C9") (pin "1") (pinfunction "1_1") (pintype "passive"))
      (node (ref "DA1") (pin "4") (pinfunction "V-_4") (pintype "passive"))
      (node (ref "DA3") (pin "4") (pinfunction "V-_4") (pintype "passive"))
      (node (ref "DA5") (pin "4") (pinfunction "V-_4") (pintype "passive"))
      (node (ref "DD1") (pin "12") (pinfunction "VSSA_12") (pintype "passive"))
      (node (ref "R2") (pin "1") (pinfunction "1_1") (pintype "passive"))
      (node (ref "X1") (pin "1") (pinfunction "1_1") (pintype "passive"))
      (node (ref "X1") (pin "8") (pinfunction "8_8") (pintype "passive"))
    )
    (net (code "63") (name "DGND") (class "Default")
      (node (ref "C10") (pin "1") (pinfunction "1_1") (pintype "passive"))
      (node (ref "C11") (pin "1") (pinfunction "1_1") (pintype "passive"))
      (node (ref "C12") (pin "1") (pinfunction "1_1") (pintype "passive"))
      (node (ref "C13") (pin "1") (pinfunction "1_1") (pintype "passive"))
      (node (ref "C14") (pin "1") (pinfunction "1_1") (pintype "passive"))
      (node (ref "C15") (pin "1") (pinfunction "1_1") (pintype "passive"))
      (node (ref "C16") (pin "1") (pinfunction "1_1") (pintype "passive"))
      (node (ref "C17") (pin "1") (pinfunction "1_1") (pintype "passive"))
      (node (ref "C18") (pin "1") (pinfunction "1_1") (pintype "passive"))
      (node (ref "C23") (pin "1") (pinfunction "1_1") (pintype "passive"))
      (node (ref "C24") (pin "1") (pinfunction "1_1") (pintype "passive"))
      (node (ref "C25") (pin "1") (pinfunction "1_1") (pintype "passive"))
      (node (ref "DA6") (pin "2") (pinfunction "GND_2") (pintype "power_in"))
      (node (ref "DA7") (pin "4") (pinfunction "GND_4") (pintype "power_in"))
      (node (ref "DD1") (pin "18") (pinfunction "VSS_4_18") (pintype "passive"))
      (node (ref "DD1") (pin "31") (pinfunction "VSS_1_31") (pintype "passive"))
      (node (ref "DD1") (pin "47") (pinfunction "VSS_2_47") (pintype "passive"))
      (node (ref "DD1") (pin "63") (pinfunction "VSS_3_63") (pintype "passive"))
      (node (ref "R10") (pin "1") (pinfunction "1_1") (pintype "passive"))
      (node (ref "R14") (pin "1") (pinfunction "1_1") (pintype "passive"))
      (node (ref "R15") (pin "1") (pinfunction "1_1") (pintype "passive"))
      (node (ref "R16") (pin "1") (pinfunction "1_1") (pintype "passive"))
      (node (ref "R17") (pin "1") (pinfunction "1_1") (pintype "passive"))
      (node (ref "R18") (pin "1") (pinfunction "1_1") (pintype "passive"))
      (node (ref "R22") (pin "1") (pinfunction "1_1") (pintype "passive"))
      (node (ref "R27") (pin "1") (pinfunction "1_1") (pintype "passive"))
      (node (ref "R28") (pin "1") (pinfunction "1_1") (pintype "passive"))
      (node (ref "R29") (pin "1") (pinfunction "1_1") (pintype "passive"))
      (node (ref "R30") (pin "1") (pinfunction "1_1") (pintype "passive"))
      (node (ref "R31") (pin "1") (pinfunction "1_1") (pintype "passive"))
      (node (ref "S1") (pin "1") (pinfunction "1_1") (pintype "passive"))
      (node (ref "SW3") (pin "2") (pintype "passive"))
      (node (ref "X3") (pin "2") (pinfunction "2_2") (pintype "passive"))
      (node (ref "X3") (pin "6") (pinfunction "6_6") (pintype "passive"))
      (node (ref "X4") (pin "16") (pinfunction "16_16") (pintype "passive"))
      (node (ref "X4") (pin "20") (pinfunction "20_20") (pintype "passive"))
      (node (ref "X4") (pin "3") (pinfunction "3_3") (pintype "passive"))
      (node (ref "X4") (pin "9") (pinfunction "9_9") (pintype "passive"))
      (node (ref "X5") (pin "15") (pinfunction "15_15") (pintype "passive"))
      (node (ref "X5") (pin "20") (pinfunction "20_20") (pintype "passive"))
      (node (ref "X5") (pin "4") (pinfunction "4_4") (pintype "passive"))
      (node (ref "X5") (pin "8") (pinfunction "8_8") (pintype "passive"))
      (node (ref "X6") (pin "3") (pinfunction "3_3") (pintype "passive"))
      (node (ref "X7") (pin "1") (pinfunction "1_1") (pintype "passive"))
      (node (ref "X7") (pin "6") (pinfunction "6_6") (pintype "passive"))
    )
    (net (code "64") (name "GND") (class "Default")
      (node (ref "C4") (pin "1") (pinfunction "1_1") (pintype "passive"))
      (node (ref "C5") (pin "1") (pinfunction "1_1") (pintype "passive"))
      (node (ref "C6") (pin "1") (pinfunction "1_1") (pintype "passive"))
      (node (ref "C7") (pin "1") (pinfunction "1_1") (pintype "passive"))
      (node (ref "DA2") (pin "2") (pinfunction "GND_2") (pintype "power_in"))
      (node (ref "DA2") (pin "4") (pinfunction "GND_4") (pintype "power_in"))
      (node (ref "DA4") (pin "2") (pinfunction "GND_2") (pintype "power_in"))
      (node (ref "DA4") (pin "4") (pinfunction "GND_4") (pintype "power_in"))
      (node (ref "R10") (pin "2") (pinfunction "5_2") (pintype "passive"))
      (node (ref "R2") (pin "2") (pinfunction "5_2") (pintype "passive"))
      (node (ref "VD3") (pin "5") (pintype "passive"))
      (node (ref "VD5") (pin "1") (pinfunction "K_1") (pintype "passive"))
      (node (ref "VD6") (pin "1") (pinfunction "K_1") (pintype "passive"))
    )
    (net (code "65") (name "Net-(DA1-+IN_A)") (class "Default")
      (node (ref "DA1") (pin "3") (pinfunction "+IN_A_3") (pintype "passive"))
      (node (ref "X1") (pin "2") (pinfunction "2_2") (pintype "passive"))
    )
    (net (code "66") (name "Net-(DA1-+IN_B)") (class "Default")
      (node (ref "DA1") (pin "5") (pinfunction "+IN_B_5") (pintype "passive"))
      (node (ref "X1") (pin "3") (pinfunction "3_3") (pintype "passive"))
    )
    (net (code "67") (name "Net-(DA3-+IN_A)") (class "Default")
      (node (ref "DA3") (pin "3") (pinfunction "+IN_A_3") (pintype "passive"))
      (node (ref "X1") (pin "4") (pinfunction "4_4") (pintype "passive"))
    )
    (net (code "68") (name "Net-(DA3-+IN_B)") (class "Default")
      (node (ref "DA3") (pin "5") (pinfunction "+IN_B_5") (pintype "passive"))
      (node (ref "X1") (pin "5") (pinfunction "5_5") (pintype "passive"))
    )
    (net (code "69") (name "Net-(DA4-IN)") (class "Default")
      (node (ref "C6") (pin "2") (pinfunction "2_2") (pintype "passive"))
      (node (ref "DA4") (pin "1") (pinfunction "IN_1") (pintype "power_in"))
      (node (ref "FU2") (pin "1") (pinfunction "1_1") (pintype "passive"))
    )
    (net (code "70") (name "Net-(DA4-OUT)") (class "Default")
      (node (ref "C7") (pin "2") (pinfunction "2_2") (pintype "passive"))
      (node (ref "DA4") (pin "3") (pinfunction "OUT_3") (pintype "power_in"))
      (node (ref "VD4") (pin "2") (pinfunction "A_2") (pintype "passive"))
    )
    (net (code "71") (name "Net-(DA5-+IN_A)") (class "Default")
      (node (ref "DA5") (pin "3") (pinfunction "+IN_A_3") (pintype "passive"))
      (node (ref "X1") (pin "6") (pinfunction "6_6") (pintype "passive"))
    )
    (net (code "72") (name "Net-(DA5-+IN_B)") (class "Default")
      (node (ref "DA5") (pin "5") (pinfunction "+IN_B_5") (pintype "passive"))
      (node (ref "X1") (pin "7") (pinfunction "7_7") (pintype "passive"))
    )
    (net (code "73") (name "Net-(DA6-CANH)") (class "Default")
      (node (ref "DA6") (pin "7") (pinfunction "CANH_7") (pintype "power_in"))
      (node (ref "SW2") (pin "2") (pintype "passive"))
      (node (ref "X6") (pin "1") (pinfunction "1_1") (pintype "passive"))
    )
    (net (code "74") (name "Net-(DA6-CANL)") (class "Default")
      (node (ref "DA6") (pin "6") (pinfunction "CANL_6") (pintype "power_in"))
      (node (ref "R19") (pin "1") (pinfunction "1_1") (pintype "passive"))
      (node (ref "X6") (pin "2") (pinfunction "2_2") (pintype "passive"))
    )
    (net (code "75") (name "Net-(DA6-D)") (class "Default")
      (node (ref "DA6") (pin "1") (pinfunction "D_1") (pintype "power_in"))
      (node (ref "R20") (pin "1") (pinfunction "1_1") (pintype "passive"))
    )
    (net (code "76") (name "Net-(DA6-R)") (class "Default")
      (node (ref "DA6") (pin "4") (pinfunction "R_4") (pintype "power_in"))
      (node (ref "R21") (pin "2") (pinfunction "5_2") (pintype "passive"))
    )
    (net (code "77") (name "Net-(DA6-Rs)") (class "Default")
      (node (ref "DA6") (pin "8") (pinfunction "Rs_8") (pintype "power_in"))
      (node (ref "R22") (pin "2") (pinfunction "5_2") (pintype "passive"))
      (node (ref "SW3") (pin "1") (pintype "passive"))
    )
    (net (code "78") (name "Net-(DA7-C1+)") (class "Default")
      (node (ref "C21") (pin "2") (pinfunction "2_2") (pintype "passive"))
      (node (ref "DA7") (pin "1") (pinfunction "C1+_1") (pintype "power_in"))
    )
    (net (code "79") (name "Net-(DA7-C1-)") (class "Default")
      (node (ref "C21") (pin "1") (pinfunction "1_1") (pintype "passive"))
      (node (ref "DA7") (pin "3") (pinfunction "C1-_3") (pintype "power_in"))
    )
    (net (code "80") (name "Net-(DA7-C2+)") (class "Default")
      (node (ref "C22") (pin "2") (pinfunction "2_2") (pintype "passive"))
      (node (ref "DA7") (pin "19") (pinfunction "C2+_19") (pintype "power_in"))
    )
    (net (code "81") (name "Net-(DA7-C2-)") (class "Default")
      (node (ref "C22") (pin "1") (pinfunction "1_1") (pintype "passive"))
      (node (ref "DA7") (pin "18") (pinfunction "C2-_18") (pintype "power_in"))
    )
    (net (code "82") (name "Net-(DA7-DE485{slash}T2IN)") (class "Default")
      (node (ref "DA7") (pin "15") (pinfunction "DE485/T2IN_15") (pintype "power_in"))
      (node (ref "R24") (pin "2") (pinfunction "5_2") (pintype "passive"))
    )
    (net (code "83") (name "Net-(DA7-DI{slash}T1IN)") (class "Default")
      (node (ref "DA7") (pin "16") (pinfunction "DI/T1IN_16") (pintype "power_in"))
      (node (ref "R23") (pin "1") (pinfunction "1_1") (pintype "passive"))
    )
    (net (code "84") (name "Net-(DA7-HDPLX)") (class "Default")
      (node (ref "DA7") (pin "12") (pinfunction "HDPLX_12") (pintype "power_in"))
      (node (ref "R31") (pin "2") (pinfunction "5_2") (pintype "passive"))
      (node (ref "SW5") (pin "1") (pintype "passive"))
    )
    (net (code "85") (name "Net-(DA7-R0{slash}R2OUT)") (class "Default")
      (node (ref "DA7") (pin "8") (pinfunction "R0/R2OUT_8") (pintype "power_in"))
      (node (ref "R26") (pin "2") (pinfunction "5_2") (pintype "passive"))
    )
    (net (code "86") (name "Net-(DA7-R1OUT)") (class "Default")
      (node (ref "DA7") (pin "7") (pinfunction "R1OUT_7") (pintype "power_in"))
      (node (ref "R25") (pin "1") (pinfunction "1_1") (pintype "passive"))
    )
    (net (code "87") (name "Net-(DA7-RS485{slash}R~{S232})") (class "Default")
      (node (ref "DA7") (pin "11") (pinfunction "RS485/R~{S232}_11") (pintype "power_in"))
      (node (ref "R30") (pin "2") (pinfunction "5_2") (pintype "passive"))
      (node (ref "SW5") (pin "2") (pintype "passive"))
    )
    (net (code "88") (name "Net-(DA7-V+)") (class "Default")
      (node (ref "C24") (pin "2") (pinfunction "2_2") (pintype "passive"))
      (node (ref "DA7") (pin "20") (pinfunction "V+_20") (pintype "power_in"))
    )
    (net (code "89") (name "Net-(DA7-V-)") (class "Default")
      (node (ref "C25") (pin "2") (pinfunction "2_2") (pintype "passive"))
      (node (ref "DA7") (pin "17") (pinfunction "V-_17") (pintype "power_in"))
    )
    (net (code "90") (name "Net-(DD1-OSC_IN_(PD0)_{slash}_FSMC_D2_{slash}_CAN_RX)") (class "Default")
      (node (ref "C18") (pin "2") (pinfunction "2_2") (pintype "passive"))
      (node (ref "DD1") (pin "5") (pinfunction "OSC_IN_(PD0)_/_FSMC_D2_/_CAN_RX_5") (pintype "passive"))
      (node (ref "Z1") (pin "1") (pinfunction "1_1") (pintype "passive"))
    )
    (net (code "91") (name "Net-(DD1-OSC_OUT_(PD1)_{slash}_FSMC_D3_{slash}_CAN_TX)") (class "Default")
      (node (ref "C11") (pin "2") (pinfunction "2_2") (pintype "passive"))
      (node (ref "DD1") (pin "6") (pinfunction "OSC_OUT_(PD1)_/_FSMC_D3_/_CAN_TX_6") (pintype "passive"))
      (node (ref "Z1") (pin "2") (pinfunction "2_2") (pintype "passive"))
    )
    (net (code "92") (name "Net-(DD1-VDDA)") (class "Default")
      (node (ref "C19") (pin "2") (pinfunction "2_2") (pintype "passive"))
      (node (ref "C20") (pin "1") (pinfunction "1_1") (pintype "passive"))
      (node (ref "DD1") (pin "13") (pinfunction "VDDA_13") (pintype "passive"))
      (node (ref "L1") (pin "2") (pinfunction "2_2") (pintype "passive"))
    )
    (net (code "93") (name "Net-(FU1-Pad1)") (class "Default")
      (node (ref "FU1") (pin "1") (pinfunction "1_1") (pintype "passive"))
      (node (ref "X2") (pin "1") (pinfunction "1_1") (pintype "passive"))
    )
    (net (code "94") (name "Net-(R3-5)") (class "Default")
      (node (ref "C2") (pin "2") (pinfunction "2_2") (pintype "passive"))
      (node (ref "C3") (pin "1") (pinfunction "1_1") (pintype "passive"))
      (node (ref "FU1") (pin "2") (pinfunction "2_2") (pintype "passive"))
      (node (ref "R3") (pin "2") (pinfunction "5_2") (pintype "passive"))
      (node (ref "VD3") (pin "1") (pintype "passive"))
    )
    (net (code "95") (name "Net-(R6-Pad1)") (class "Default")
      (node (ref "R6") (pin "1") (pinfunction "1_1") (pintype "passive"))
      (node (ref "VD3") (pin "7") (pintype "passive"))
    )
    (net (code "96") (name "Net-(R7-5)") (class "Default")
      (node (ref "C2") (pin "1") (pinfunction "1_1") (pintype "passive"))
      (node (ref "C3") (pin "2") (pinfunction "2_2") (pintype "passive"))
      (node (ref "R7") (pin "2") (pinfunction "5_2") (pintype "passive"))
      (node (ref "VD3") (pin "4") (pintype "passive"))
      (node (ref "X2") (pin "5") (pinfunction "5_5") (pintype "passive"))
      (node (ref "X2") (pin "6") (pinfunction "6_6") (pintype "passive"))
    )
    (net (code "97") (name "Net-(R7-Pad1)") (class "Default")
      (node (ref "R7") (pin "1") (pinfunction "1_1") (pintype "passive"))
      (node (ref "X2") (pin "4") (pinfunction "4_4") (pintype "passive"))
    )
    (net (code "98") (name "Net-(R8-Pad1)") (class "Default")
      (node (ref "R8") (pin "1") (pinfunction "1_1") (pintype "passive"))
      (node (ref "VD3") (pin "6") (pintype "passive"))
    )
    (net (code "99") (name "Net-(R11-Pad1)") (class "Default")
      (node (ref "R11") (pin "1") (pinfunction "1_1") (pintype "passive"))
      (node (ref "X3") (pin "3") (pinfunction "3_3") (pintype "passive"))
    )
    (net (code "100") (name "Net-(R12-Pad1)") (class "Default")
      (node (ref "R12") (pin "1") (pinfunction "1_1") (pintype "passive"))
      (node (ref "X3") (pin "5") (pinfunction "5_5") (pintype "passive"))
    )
    (net (code "101") (name "Net-(R19-5)") (class "Default")
      (node (ref "R19") (pin "2") (pinfunction "5_2") (pintype "passive"))
      (node (ref "SW2") (pin "1") (pintype "passive"))
    )
    (net (code "102") (name "Net-(VD2-A)") (class "Default")
      (node (ref "VD2") (pin "2") (pinfunction "A_2") (pintype "passive"))
      (node (ref "VD3") (pin "8") (pintype "passive"))
    )
    (net (code "103") (name "Net-(VD5-A)") (class "Default")
      (node (ref "R4") (pin "1") (pinfunction "1_1") (pintype "passive"))
      (node (ref "VD5") (pin "2") (pinfunction "A_2") (pintype "passive"))
    )
    (net (code "104") (name "Net-(VD6-A)") (class "Default")
      (node (ref "R5") (pin "1") (pinfunction "1_1") (pintype "passive"))
      (node (ref "VD6") (pin "2") (pinfunction "A_2") (pintype "passive"))
    )
    (net (code "105") (name "Net-(VD7-K)") (class "Default")
      (node (ref "VD7") (pin "1") (pinfunction "K_1") (pintype "passive"))
      (node (ref "X3") (pin "1") (pinfunction "1_1") (pintype "passive"))
    )
    (net (code "106") (name "Net-(VD8-K)") (class "Default")
      (node (ref "VD8") (pin "1") (pinfunction "K_1") (pintype "passive"))
      (node (ref "X4") (pin "2") (pinfunction "2_2") (pintype "passive"))
    )
    (net (code "107") (name "Net-(VD9-K)") (class "Default")
      (node (ref "VD9") (pin "1") (pinfunction "K_1") (pintype "passive"))
      (node (ref "X4") (pin "1") (pinfunction "1_1") (pintype "passive"))
    )
    (net (code "108") (name "Net-(VD10-K)") (class "Default")
      (node (ref "VD10") (pin "1") (pinfunction "K_1") (pintype "passive"))
      (node (ref "X5") (pin "3") (pinfunction "3_3") (pintype "passive"))
    )
    (net (code "109") (name "Net-(VD11-K)") (class "Default")
      (node (ref "VD11") (pin "1") (pinfunction "K_1") (pintype "passive"))
      (node (ref "X5") (pin "2") (pinfunction "2_2") (pintype "passive"))
    )
    (net (code "110") (name "VIN") (class "Default")
      (node (ref "FU2") (pin "2") (pinfunction "2_2") (pintype "passive"))
      (node (ref "X5") (pin "1") (pinfunction "1_1") (pintype "passive"))
    )
    (net (code "111") (name "unconnected-(DA6-Vref-Pad5)") (class "Default")
      (node (ref "DA6") (pin "5") (pinfunction "Vref_5") (pintype "power_in"))
    )
  )
)
